# motor_driver_LM5107.net
KiCad netlist of a schematic drawn in EAGLE
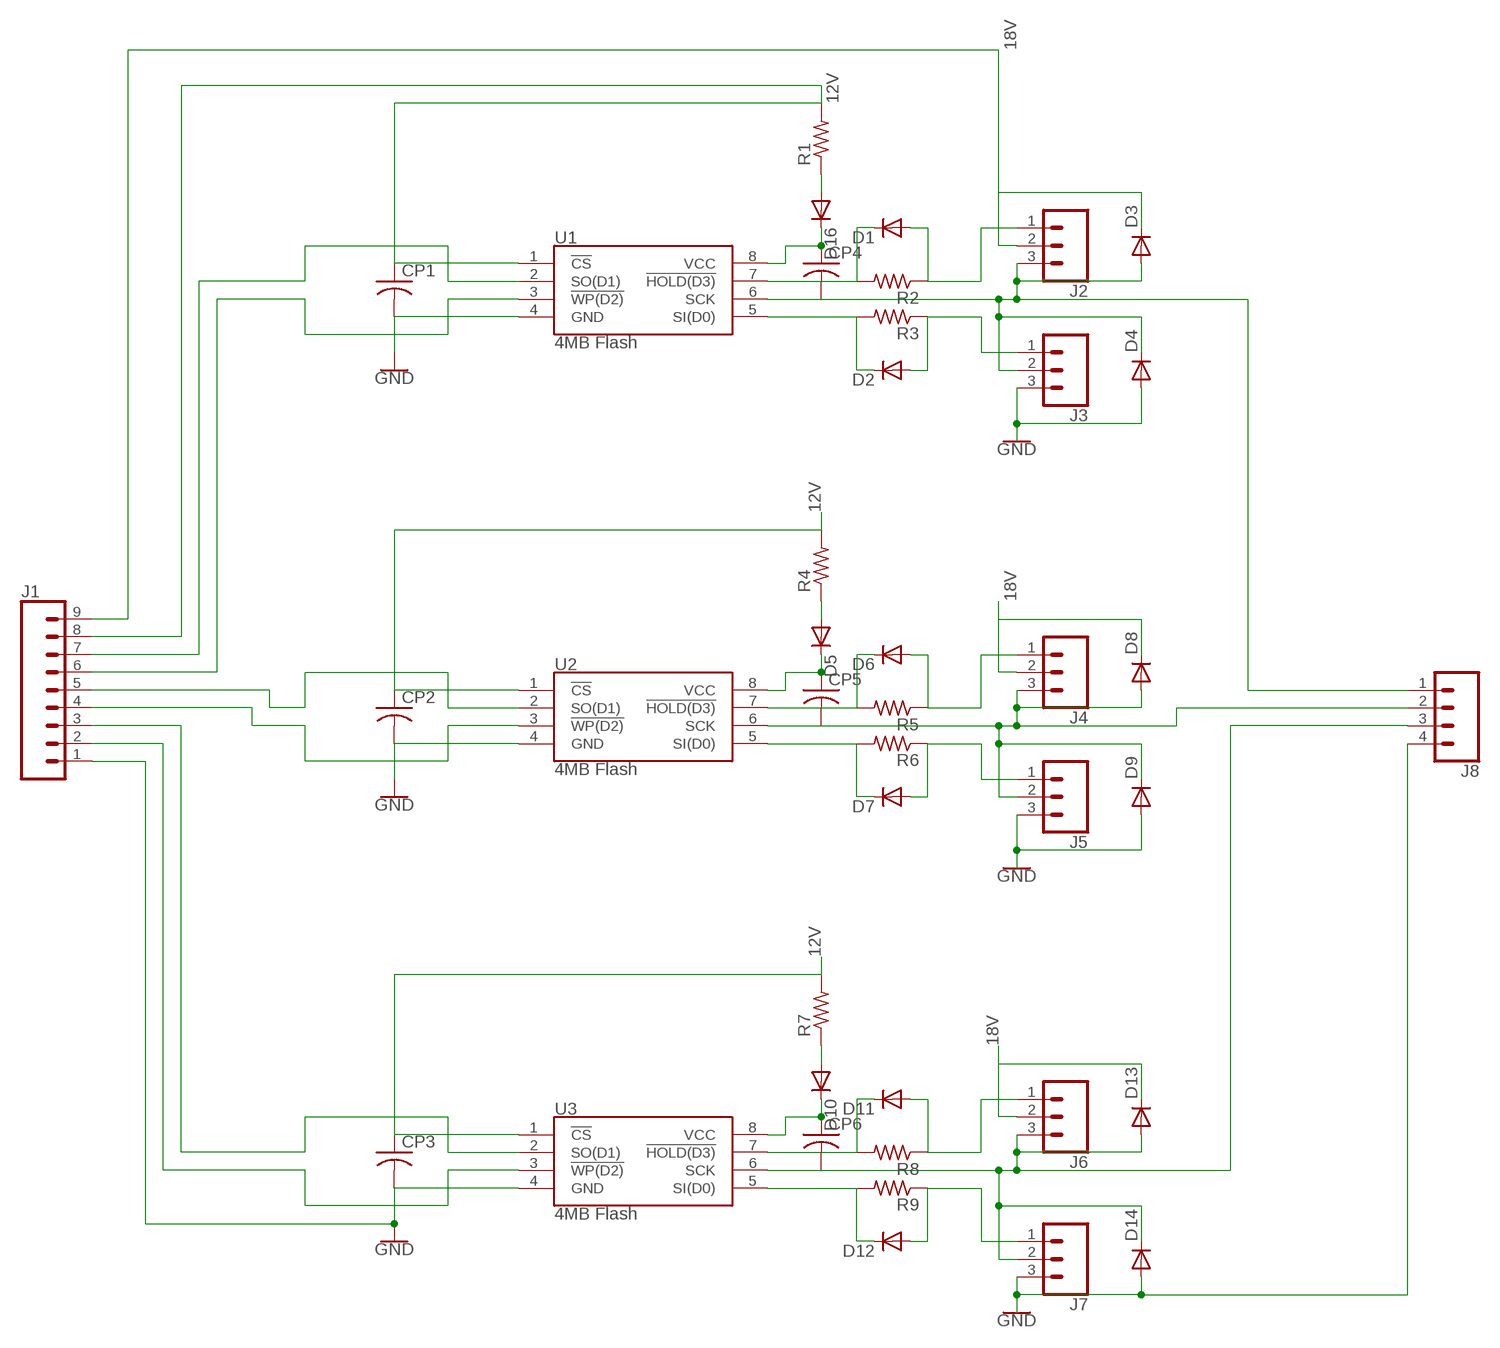
[diagram p0: schematic, sheet 1]

(export (version "E")
  (design (tool "Eeschema 10.0.6"))
  (components
    (comp (ref "CP1")
      (value "C-US025-024X044")
      (footprint "eagle-import:C025-024X044")
      (libsource (lib "eagle-import") (part "C-US025-024X044"))
    )
    (comp (ref "CP2")
      (value "C-US025-024X044")
      (footprint "eagle-import:C025-024X044")
      (libsource (lib "eagle-import") (part "C-US025-024X044"))
    )
    (comp (ref "CP3")
      (value "C-US025-024X044")
      (footprint "eagle-import:C025-024X044")
      (libsource (lib "eagle-import") (part "C-US025-024X044"))
    )
    (comp (ref "CP4")
      (value "C-US025-024X044")
      (footprint "eagle-import:C025-024X044")
      (libsource (lib "eagle-import") (part "C-US025-024X044"))
    )
    (comp (ref "CP5")
      (value "C-US025-024X044")
      (footprint "eagle-import:C025-024X044")
      (libsource (lib "eagle-import") (part "C-US025-024X044"))
    )
    (comp (ref "CP6")
      (value "C-US025-024X044")
      (footprint "eagle-import:C025-024X044")
      (libsource (lib "eagle-import") (part "C-US025-024X044"))
    )
    (comp (ref "D1")
      (value "DIODE-D-5")
      (footprint "eagle-import:D-5")
      (libsource (lib "eagle-import") (part "DIODE-D-5"))
    )
    (comp (ref "D2")
      (value "DIODE-D-5")
      (footprint "eagle-import:D-5")
      (libsource (lib "eagle-import") (part "DIODE-D-5"))
    )
    (comp (ref "D3")
      (value "DIODE-D-5")
      (footprint "eagle-import:D-5")
      (libsource (lib "eagle-import") (part "DIODE-D-5"))
    )
    (comp (ref "D4")
      (value "DIODE-D-5")
      (footprint "eagle-import:D-5")
      (libsource (lib "eagle-import") (part "DIODE-D-5"))
    )
    (comp (ref "D5")
      (value "DIODE-D-5")
      (footprint "eagle-import:D-5")
      (libsource (lib "eagle-import") (part "DIODE-D-5"))
    )
    (comp (ref "D6")
      (value "DIODE-D-5")
      (footprint "eagle-import:D-5")
      (libsource (lib "eagle-import") (part "DIODE-D-5"))
    )
    (comp (ref "D7")
      (value "DIODE-D-5")
      (footprint "eagle-import:D-5")
      (libsource (lib "eagle-import") (part "DIODE-D-5"))
    )
    (comp (ref "D8")
      (value "DIODE-D-5")
      (footprint "eagle-import:D-5")
      (libsource (lib "eagle-import") (part "DIODE-D-5"))
    )
    (comp (ref "D9")
      (value "DIODE-D-5")
      (footprint "eagle-import:D-5")
      (libsource (lib "eagle-import") (part "DIODE-D-5"))
    )
    (comp (ref "D10")
      (value "DIODE-D-5")
      (footprint "eagle-import:D-5")
      (libsource (lib "eagle-import") (part "DIODE-D-5"))
    )
    (comp (ref "D11")
      (value "DIODE-D-5")
      (footprint "eagle-import:D-5")
      (libsource (lib "eagle-import") (part "DIODE-D-5"))
    )
    (comp (ref "D12")
      (value "DIODE-D-5")
      (footprint "eagle-import:D-5")
      (libsource (lib "eagle-import") (part "DIODE-D-5"))
    )
    (comp (ref "D13")
      (value "DIODE-D-5")
      (footprint "eagle-import:D-5")
      (libsource (lib "eagle-import") (part "DIODE-D-5"))
    )
    (comp (ref "D14")
      (value "DIODE-D-5")
      (footprint "eagle-import:D-5")
      (libsource (lib "eagle-import") (part "DIODE-D-5"))
    )
    (comp (ref "D16")
      (value "DIODE-D-5")
      (footprint "eagle-import:D-5")
      (libsource (lib "eagle-import") (part "DIODE-D-5"))
    )
    (comp (ref "J1")
      (value "CONN_09")
      (footprint "eagle-import:1X09")
      (libsource (lib "eagle-import") (part "CONN_09"))
    )
    (comp (ref "J2")
      (value "CONN_03LOCK")
      (footprint "eagle-import:1X03_LOCK")
      (libsource (lib "eagle-import") (part "CONN_03LOCK"))
    )
    (comp (ref "J3")
      (value "CONN_03LOCK")
      (footprint "eagle-import:1X03_LOCK")
      (libsource (lib "eagle-import") (part "CONN_03LOCK"))
    )
    (comp (ref "J4")
      (value "CONN_03LOCK")
      (footprint "eagle-import:1X03_LOCK")
      (libsource (lib "eagle-import") (part "CONN_03LOCK"))
    )
    (comp (ref "J5")
      (value "CONN_03LOCK")
      (footprint "eagle-import:1X03_LOCK")
      (libsource (lib "eagle-import") (part "CONN_03LOCK"))
    )
    (comp (ref "J6")
      (value "CONN_03LOCK")
      (footprint "eagle-import:1X03_LOCK")
      (libsource (lib "eagle-import") (part "CONN_03LOCK"))
    )
    (comp (ref "J7")
      (value "CONN_03LOCK")
      (footprint "eagle-import:1X03_LOCK")
      (libsource (lib "eagle-import") (part "CONN_03LOCK"))
    )
    (comp (ref "J8")
      (value "CONN_04")
      (footprint "eagle-import:1X04")
      (libsource (lib "eagle-import") (part "CONN_04"))
    )
    (comp (ref "R1")
      (value "R-US_0204/5")
      (footprint "eagle-import:0204_5")
      (libsource (lib "eagle-import") (part "R-US_0204/5"))
    )
    (comp (ref "R2")
      (value "R-US_0204/5")
      (footprint "eagle-import:0204_5")
      (libsource (lib "eagle-import") (part "R-US_0204/5"))
    )
    (comp (ref "R3")
      (value "R-US_0204/5")
      (footprint "eagle-import:0204_5")
      (libsource (lib "eagle-import") (part "R-US_0204/5"))
    )
    (comp (ref "R4")
      (value "R-US_0204/5")
      (footprint "eagle-import:0204_5")
      (libsource (lib "eagle-import") (part "R-US_0204/5"))
    )
    (comp (ref "R5")
      (value "R-US_0204/5")
      (footprint "eagle-import:0204_5")
      (libsource (lib "eagle-import") (part "R-US_0204/5"))
    )
    (comp (ref "R6")
      (value "R-US_0204/5")
      (footprint "eagle-import:0204_5")
      (libsource (lib "eagle-import") (part "R-US_0204/5"))
    )
    (comp (ref "R7")
      (value "R-US_0204/5")
      (footprint "eagle-import:0204_5")
      (libsource (lib "eagle-import") (part "R-US_0204/5"))
    )
    (comp (ref "R8")
      (value "R-US_0204/5")
      (footprint "eagle-import:0204_5")
      (libsource (lib "eagle-import") (part "R-US_0204/5"))
    )
    (comp (ref "R9")
      (value "R-US_0204/5")
      (footprint "eagle-import:0204_5")
      (libsource (lib "eagle-import") (part "R-US_0204/5"))
    )
    (comp (ref "U1")
      (value "4MB Flash")
      (footprint "eagle-import:SO08")
      (libsource (lib "eagle-import") (part "AT25SF041"))
    )
    (comp (ref "U2")
      (value "4MB Flash")
      (footprint "eagle-import:SO08")
      (libsource (lib "eagle-import") (part "AT25SF041"))
    )
    (comp (ref "U3")
      (value "4MB Flash")
      (footprint "eagle-import:SO08")
      (libsource (lib "eagle-import") (part "AT25SF041"))
    )
  )
  (nets
    (net (code "1") (name "/12V") (class "Default")
      (node (ref "CP1") (pin "1") (pinfunction "1_1") (pintype "passive"))
      (node (ref "CP2") (pin "1") (pinfunction "1_1") (pintype "passive"))
      (node (ref "CP3") (pin "1") (pinfunction "1_1") (pintype "passive"))
      (node (ref "J1") (pin "8") (pinfunction "8_8") (pintype "passive"))
      (node (ref "R1") (pin "2") (pinfunction "2_2") (pintype "passive"))
      (node (ref "R4") (pin "2") (pinfunction "2_2") (pintype "passive"))
      (node (ref "R7") (pin "2") (pinfunction "2_2") (pintype "passive"))
      (node (ref "U1") (pin "1") (pinfunction "~{CS}_1") (pintype "bidirectional"))
      (node (ref "U2") (pin "1") (pinfunction "~{CS}_1") (pintype "bidirectional"))
      (node (ref "U3") (pin "1") (pinfunction "~{CS}_1") (pintype "bidirectional"))
    )
    (net (code "2") (name "/18V") (class "Default")
      (node (ref "D13") (pin "C") (pinfunction "C_C") (pintype "passive"))
      (node (ref "D3") (pin "C") (pinfunction "C_C") (pintype "passive"))
      (node (ref "D8") (pin "C") (pinfunction "C_C") (pintype "passive"))
      (node (ref "J1") (pin "9") (pinfunction "9_9") (pintype "passive"))
      (node (ref "J2") (pin "2") (pinfunction "2_2") (pintype "passive"))
      (node (ref "J4") (pin "2") (pinfunction "2_2") (pintype "passive"))
      (node (ref "J6") (pin "2") (pinfunction "2_2") (pintype "passive"))
    )
    (net (code "3") (name "GND") (class "Default")
      (node (ref "CP1") (pin "2") (pinfunction "2_2") (pintype "passive"))
      (node (ref "CP2") (pin "2") (pinfunction "2_2") (pintype "passive"))
      (node (ref "CP3") (pin "2") (pinfunction "2_2") (pintype "passive"))
      (node (ref "D14") (pin "A") (pinfunction "A_A") (pintype "passive"))
      (node (ref "D4") (pin "A") (pinfunction "A_A") (pintype "passive"))
      (node (ref "D9") (pin "A") (pinfunction "A_A") (pintype "passive"))
      (node (ref "J1") (pin "1") (pinfunction "1_1") (pintype "passive"))
      (node (ref "J3") (pin "3") (pinfunction "3_3") (pintype "passive"))
      (node (ref "J5") (pin "3") (pinfunction "3_3") (pintype "passive"))
      (node (ref "J7") (pin "3") (pinfunction "3_3") (pintype "passive"))
      (node (ref "J8") (pin "4") (pinfunction "4_4") (pintype "passive"))
      (node (ref "U1") (pin "4") (pinfunction "GND_4") (pintype "bidirectional"))
      (node (ref "U2") (pin "4") (pinfunction "GND_4") (pintype "bidirectional"))
      (node (ref "U3") (pin "4") (pinfunction "GND_4") (pintype "bidirectional"))
    )
    (net (code "4") (name "Net-(D1-PadA)") (class "Default")
      (node (ref "D1") (pin "A") (pinfunction "A_A") (pintype "passive"))
      (node (ref "J2") (pin "1") (pinfunction "1_1") (pintype "passive"))
      (node (ref "R2") (pin "1") (pinfunction "1_1") (pintype "passive"))
    )
    (net (code "5") (name "Net-(D2-PadA)") (class "Default")
      (node (ref "D2") (pin "A") (pinfunction "A_A") (pintype "passive"))
      (node (ref "J3") (pin "1") (pinfunction "1_1") (pintype "passive"))
      (node (ref "R3") (pin "1") (pinfunction "1_1") (pintype "passive"))
    )
    (net (code "6") (name "Net-(D5-PadA)") (class "Default")
      (node (ref "D5") (pin "A") (pinfunction "A_A") (pintype "passive"))
      (node (ref "R4") (pin "1") (pinfunction "1_1") (pintype "passive"))
    )
    (net (code "7") (name "Net-(D6-PadA)") (class "Default")
      (node (ref "D6") (pin "A") (pinfunction "A_A") (pintype "passive"))
      (node (ref "J4") (pin "1") (pinfunction "1_1") (pintype "passive"))
      (node (ref "R5") (pin "1") (pinfunction "1_1") (pintype "passive"))
    )
    (net (code "8") (name "Net-(D7-PadA)") (class "Default")
      (node (ref "D7") (pin "A") (pinfunction "A_A") (pintype "passive"))
      (node (ref "J5") (pin "1") (pinfunction "1_1") (pintype "passive"))
      (node (ref "R6") (pin "1") (pinfunction "1_1") (pintype "passive"))
    )
    (net (code "9") (name "Net-(D10-PadA)") (class "Default")
      (node (ref "D10") (pin "A") (pinfunction "A_A") (pintype "passive"))
      (node (ref "R7") (pin "1") (pinfunction "1_1") (pintype "passive"))
    )
    (net (code "10") (name "Net-(D11-PadA)") (class "Default")
      (node (ref "D11") (pin "A") (pinfunction "A_A") (pintype "passive"))
      (node (ref "J6") (pin "1") (pinfunction "1_1") (pintype "passive"))
      (node (ref "R8") (pin "1") (pinfunction "1_1") (pintype "passive"))
    )
    (net (code "11") (name "Net-(D12-PadA)") (class "Default")
      (node (ref "D12") (pin "A") (pinfunction "A_A") (pintype "passive"))
      (node (ref "J7") (pin "1") (pinfunction "1_1") (pintype "passive"))
      (node (ref "R9") (pin "1") (pinfunction "1_1") (pintype "passive"))
    )
    (net (code "12") (name "Net-(D16-PadA)") (class "Default")
      (node (ref "D16") (pin "A") (pinfunction "A_A") (pintype "passive"))
      (node (ref "R1") (pin "1") (pinfunction "1_1") (pintype "passive"))
    )
    (net (code "13") (name "Net-(U1-SCK)") (class "Default")
      (node (ref "CP4") (pin "2") (pinfunction "2_2") (pintype "passive"))
      (node (ref "D3") (pin "A") (pinfunction "A_A") (pintype "passive"))
      (node (ref "D4") (pin "C") (pinfunction "C_C") (pintype "passive"))
      (node (ref "J2") (pin "3") (pinfunction "3_3") (pintype "passive"))
      (node (ref "J3") (pin "2") (pinfunction "2_2") (pintype "passive"))
      (node (ref "J8") (pin "1") (pinfunction "1_1") (pintype "passive"))
      (node (ref "U1") (pin "6") (pinfunction "SCK_6") (pintype "bidirectional"))
    )
    (net (code "14") (name "Net-(U1-SI(D0))") (class "Default")
      (node (ref "D2") (pin "C") (pinfunction "C_C") (pintype "passive"))
      (node (ref "R3") (pin "2") (pinfunction "2_2") (pintype "passive"))
      (node (ref "U1") (pin "5") (pinfunction "SI(D0)_5") (pintype "bidirectional"))
    )
    (net (code "15") (name "Net-(U1-SO(D1))") (class "Default")
      (node (ref "J1") (pin "7") (pinfunction "7_7") (pintype "passive"))
      (node (ref "U1") (pin "2") (pinfunction "SO(D1)_2") (pintype "bidirectional"))
    )
    (net (code "16") (name "Net-(U1-VCC)") (class "Default")
      (node (ref "CP4") (pin "1") (pinfunction "1_1") (pintype "passive"))
      (node (ref "D16") (pin "C") (pinfunction "C_C") (pintype "passive"))
      (node (ref "U1") (pin "8") (pinfunction "VCC_8") (pintype "bidirectional"))
    )
    (net (code "17") (name "Net-(U1-~{HOLD(D3}))") (class "Default")
      (node (ref "D1") (pin "C") (pinfunction "C_C") (pintype "passive"))
      (node (ref "R2") (pin "2") (pinfunction "2_2") (pintype "passive"))
      (node (ref "U1") (pin "7") (pinfunction "~{HOLD(D3})_7") (pintype "bidirectional"))
    )
    (net (code "18") (name "Net-(U1-~{WP(D2}))") (class "Default")
      (node (ref "J1") (pin "6") (pinfunction "6_6") (pintype "passive"))
      (node (ref "U1") (pin "3") (pinfunction "~{WP(D2})_3") (pintype "bidirectional"))
    )
    (net (code "19") (name "Net-(U2-SCK)") (class "Default")
      (node (ref "CP5") (pin "2") (pinfunction "2_2") (pintype "passive"))
      (node (ref "D8") (pin "A") (pinfunction "A_A") (pintype "passive"))
      (node (ref "D9") (pin "C") (pinfunction "C_C") (pintype "passive"))
      (node (ref "J4") (pin "3") (pinfunction "3_3") (pintype "passive"))
      (node (ref "J5") (pin "2") (pinfunction "2_2") (pintype "passive"))
      (node (ref "J8") (pin "2") (pinfunction "2_2") (pintype "passive"))
      (node (ref "U2") (pin "6") (pinfunction "SCK_6") (pintype "bidirectional"))
    )
    (net (code "20") (name "Net-(U2-SI(D0))") (class "Default")
      (node (ref "D7") (pin "C") (pinfunction "C_C") (pintype "passive"))
      (node (ref "R6") (pin "2") (pinfunction "2_2") (pintype "passive"))
      (node (ref "U2") (pin "5") (pinfunction "SI(D0)_5") (pintype "bidirectional"))
    )
    (net (code "21") (name "Net-(U2-SO(D1))") (class "Default")
      (node (ref "J1") (pin "5") (pinfunction "5_5") (pintype "passive"))
      (node (ref "U2") (pin "2") (pinfunction "SO(D1)_2") (pintype "bidirectional"))
    )
    (net (code "22") (name "Net-(U2-VCC)") (class "Default")
      (node (ref "CP5") (pin "1") (pinfunction "1_1") (pintype "passive"))
      (node (ref "D5") (pin "C") (pinfunction "C_C") (pintype "passive"))
      (node (ref "U2") (pin "8") (pinfunction "VCC_8") (pintype "bidirectional"))
    )
    (net (code "23") (name "Net-(U2-~{HOLD(D3}))") (class "Default")
      (node (ref "D6") (pin "C") (pinfunction "C_C") (pintype "passive"))
      (node (ref "R5") (pin "2") (pinfunction "2_2") (pintype "passive"))
      (node (ref "U2") (pin "7") (pinfunction "~{HOLD(D3})_7") (pintype "bidirectional"))
    )
    (net (code "24") (name "Net-(U2-~{WP(D2}))") (class "Default")
      (node (ref "J1") (pin "4") (pinfunction "4_4") (pintype "passive"))
      (node (ref "U2") (pin "3") (pinfunction "~{WP(D2})_3") (pintype "bidirectional"))
    )
    (net (code "25") (name "Net-(U3-SCK)") (class "Default")
      (node (ref "CP6") (pin "2") (pinfunction "2_2") (pintype "passive"))
      (node (ref "D13") (pin "A") (pinfunction "A_A") (pintype "passive"))
      (node (ref "D14") (pin "C") (pinfunction "C_C") (pintype "passive"))
      (node (ref "J6") (pin "3") (pinfunction "3_3") (pintype "passive"))
      (node (ref "J7") (pin "2") (pinfunction "2_2") (pintype "passive"))
      (node (ref "J8") (pin "3") (pinfunction "3_3") (pintype "passive"))
      (node (ref "U3") (pin "6") (pinfunction "SCK_6") (pintype "bidirectional"))
    )
    (net (code "26") (name "Net-(U3-SI(D0))") (class "Default")
      (node (ref "D12") (pin "C") (pinfunction "C_C") (pintype "passive"))
      (node (ref "R9") (pin "2") (pinfunction "2_2") (pintype "passive"))
      (node (ref "U3") (pin "5") (pinfunction "SI(D0)_5") (pintype "bidirectional"))
    )
    (net (code "27") (name "Net-(U3-SO(D1))") (class "Default")
      (node (ref "J1") (pin "3") (pinfunction "3_3") (pintype "passive"))
      (node (ref "U3") (pin "2") (pinfunction "SO(D1)_2") (pintype "bidirectional"))
    )
    (net (code "28") (name "Net-(U3-VCC)") (class "Default")
      (node (ref "CP6") (pin "1") (pinfunction "1_1") (pintype "passive"))
      (node (ref "D10") (pin "C") (pinfunction "C_C") (pintype "passive"))
      (node (ref "U3") (pin "8") (pinfunction "VCC_8") (pintype "bidirectional"))
    )
    (net (code "29") (name "Net-(U3-~{HOLD(D3}))") (class "Default")
      (node (ref "D11") (pin "C") (pinfunction "C_C") (pintype "passive"))
      (node (ref "R8") (pin "2") (pinfunction "2_2") (pintype "passive"))
      (node (ref "U3") (pin "7") (pinfunction "~{HOLD(D3})_7") (pintype "bidirectional"))
    )
    (net (code "30") (name "Net-(U3-~{WP(D2}))") (class "Default")
      (node (ref "J1") (pin "2") (pinfunction "2_2") (pintype "passive"))
      (node (ref "U3") (pin "3") (pinfunction "~{WP(D2})_3") (pintype "bidirectional"))
    )
  )
)
